# master.net
KiCad netlist of a schematic drawn in Altium Designer
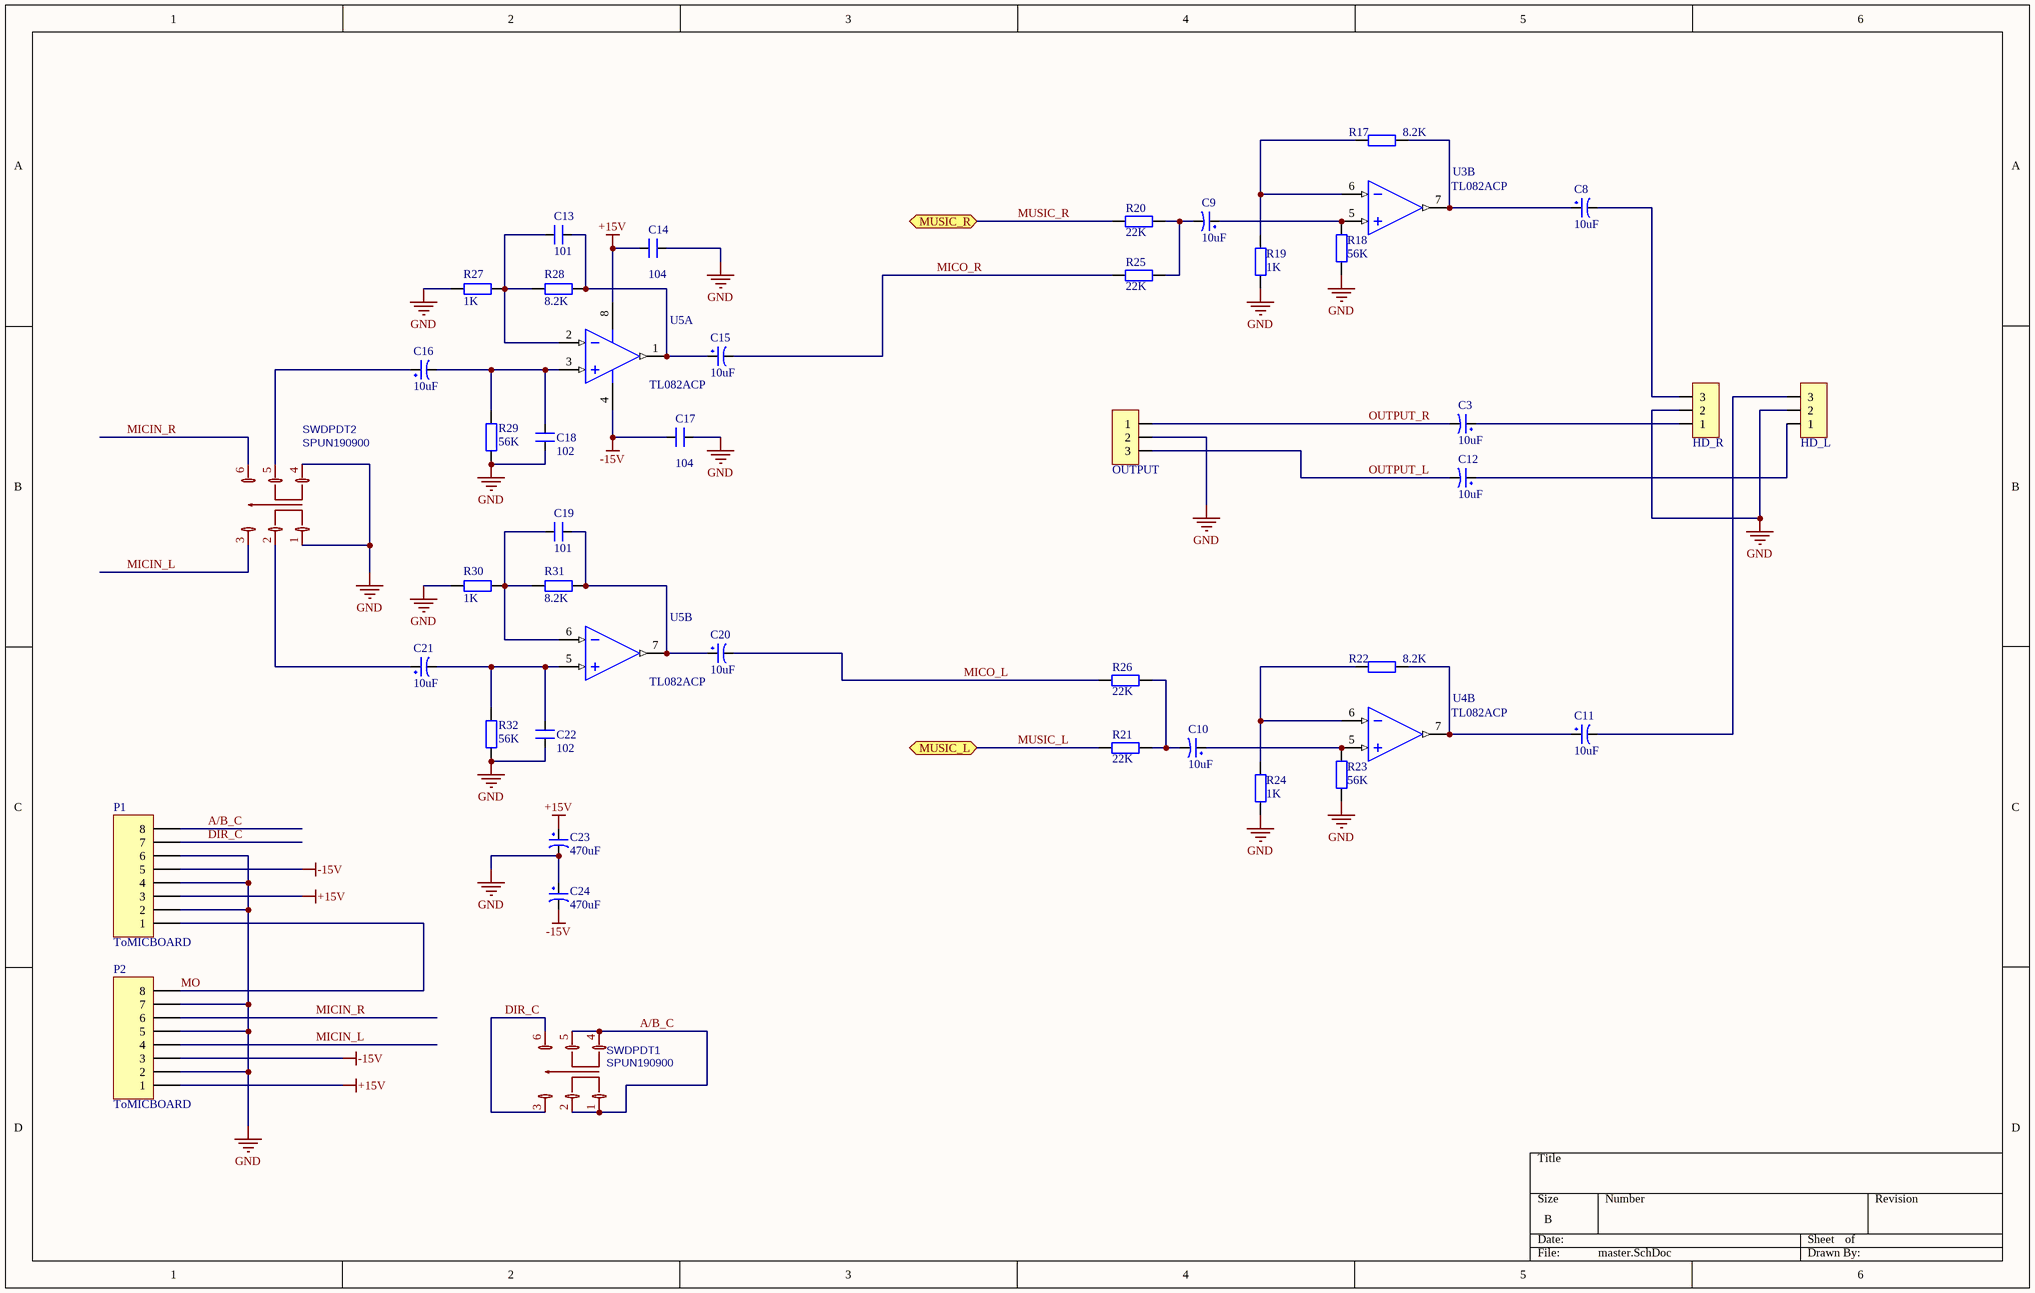
[diagram p0: master.SchDoc]

(export (version "E")
  (design (tool "Eeschema 10.0.6"))
  (components
    (comp (ref "C3")
      (value "10uF")
      (footprint "CAP5x12")
      (description "TU_HOA_4.7uF_100V_MH")
      (libsource (lib "MH_DA_THU_VIEN_16122016") (part "TU_HOA_4.7uF_100V_MH"))
    )
    (comp (ref "C8")
      (value "10uF")
      (footprint "CAP5x12")
      (description "TU_HOA_4.7uF_100V_MH")
      (libsource (lib "MH_DA_THU_VIEN_16122016") (part "TU_HOA_4.7uF_100V_MH"))
    )
    (comp (ref "C9")
      (value "10uF")
      (footprint "CAP5x12")
      (description "TU_HOA_4.7uF_100V_MH")
      (libsource (lib "MH_DA_THU_VIEN_16122016") (part "TU_HOA_4.7uF_100V_MH"))
    )
    (comp (ref "C10")
      (value "10uF")
      (footprint "CAP5x12")
      (description "TU_HOA_4.7uF_100V_MH")
      (libsource (lib "MH_DA_THU_VIEN_16122016") (part "TU_HOA_4.7uF_100V_MH"))
    )
    (comp (ref "C11")
      (value "10uF")
      (footprint "CAP5x12")
      (description "TU_HOA_4.7uF_100V_MH")
      (libsource (lib "MH_DA_THU_VIEN_16122016") (part "TU_HOA_4.7uF_100V_MH"))
    )
    (comp (ref "C12")
      (value "10uF")
      (footprint "CAP5x12")
      (description "TU_HOA_4.7uF_100V_MH")
      (libsource (lib "MH_DA_THU_VIEN_16122016") (part "TU_HOA_4.7uF_100V_MH"))
    )
    (comp (ref "C13")
      (value "101")
      (footprint "TU_GOM(104-->105pF)")
      (libsource (lib "MH_DA_THU_VIEN_16122016") (part "TU_GOM(104 ={gt} 105pF)_MH"))
    )
    (comp (ref "C14")
      (value "104")
      (footprint "TU_GOM(104-->105pF)")
      (libsource (lib "MH_DA_THU_VIEN_16122016") (part "TU_MICA_ 104 100V(2A104J)_MH"))
    )
    (comp (ref "C15")
      (value "10uF")
      (footprint "CAP5x12")
      (description "TU_HOA_4.7uF_100V_MH")
      (libsource (lib "MH_DA_THU_VIEN_16122016") (part "TU_HOA_4.7uF_100V_MH"))
    )
    (comp (ref "C16")
      (value "10uF")
      (footprint "CAP5x12")
      (libsource (lib "MH_DA_THU_VIEN_16122016") (part "TU_HOA_10uF_16V_MH"))
    )
    (comp (ref "C17")
      (value "104")
      (footprint "TU_GOM(104-->105pF)")
      (libsource (lib "MH_DA_THU_VIEN_16122016") (part "TU_MICA_ 104 100V(2A104J)_MH"))
    )
    (comp (ref "C18")
      (value "102")
      (footprint "TU_GOM(104-->105pF)")
      (libsource (lib "MH_DA_THU_VIEN_16122016") (part "TU_GOM(104 ={gt} 105pF)_MH"))
    )
    (comp (ref "C19")
      (value "101")
      (footprint "TU_GOM(104-->105pF)")
      (libsource (lib "MH_DA_THU_VIEN_16122016") (part "TU_GOM(104 ={gt} 105pF)_MH"))
    )
    (comp (ref "C20")
      (value "10uF")
      (footprint "CAP5x12")
      (description "TU_HOA_4.7uF_100V_MH")
      (libsource (lib "MH_DA_THU_VIEN_16122016") (part "TU_HOA_4.7uF_100V_MH"))
    )
    (comp (ref "C21")
      (value "10uF")
      (footprint "CAP5x12")
      (libsource (lib "MH_DA_THU_VIEN_16122016") (part "TU_HOA_10uF_16V_MH"))
    )
    (comp (ref "C22")
      (value "102")
      (footprint "TU_GOM(104-->105pF)")
      (libsource (lib "MH_DA_THU_VIEN_16122016") (part "TU_GOM(104 ={gt} 105pF)_MH"))
    )
    (comp (ref "C23")
      (value "470uF")
      (footprint "TU_HOA(100uF/35V - 470uF/16V)")
      (description "10uF")
      (libsource (lib "") (part "TU_HOA_10uF_16V_MH_1"))
    )
    (comp (ref "C24")
      (value "470uF")
      (footprint "TU_HOA(100uF/35V - 470uF/16V)")
      (description "10uF")
      (libsource (lib "") (part "TU_HOA_10uF_16V_MH_1"))
    )
    (comp (ref "HD_L")
      (value "Header 3_MH")
      (footprint "HEADER 3")
      (description "Header 3P XH2.54 thẳng")
      (libsource (lib "MH_DA_THU_VIEN_16122016") (part "Header 3_MH"))
    )
    (comp (ref "HD_R")
      (value "Header 3_MH")
      (footprint "HEADER 3")
      (description "Header 3P XH2.54 thẳng")
      (libsource (lib "MH_DA_THU_VIEN_16122016") (part "Header 3_MH"))
    )
    (comp (ref "OUTPUT")
      (value "Header 3_MH")
      (footprint "HEADER 3")
      (description "Header 3P XH2.54 thẳng")
      (libsource (lib "") (part "Header 3_MH_1"))
    )
    (comp (ref "P1")
      (value "ToMICBOARD")
      (footprint "HEADER2M_8P")
      (description "Header, 8-Pin")
      (fields (field (name "PUBLISHER") "Altium Limited"))
      (libsource (lib "Miscellaneous Connectors") (part "Header 8"))
    )
    (comp (ref "P2")
      (value "ToMICBOARD")
      (footprint "HEADER 8")
      (description "Header, 8-Pin")
      (fields (field (name "PUBLISHER") "Altium Limited"))
      (libsource (lib "Miscellaneous Connectors") (part "Header 8"))
    )
    (comp (ref "R17")
      (value "8.2K")
      (footprint "TRO_VACH_ 1/4W")
      (description "Resistor")
      (fields (field (name "PUBLISHER") "Altium Limited"))
      (libsource (lib "") (part "TRO_VACH_1/2W_MH_2"))
    )
    (comp (ref "R18")
      (value "56K")
      (footprint "TRO_VACH_ 1/4W")
      (description "Resistor")
      (fields (field (name "PUBLISHER") "Altium Limited"))
      (libsource (lib "MH_DA_THU_VIEN_16122016") (part "TRO_VACH_1/2W_MH"))
    )
    (comp (ref "R19")
      (value "1K")
      (footprint "TRO_VACH_ 1/4W")
      (description "Resistor")
      (fields (field (name "PUBLISHER") "Altium Limited"))
      (libsource (lib "MH_DA_THU_VIEN_16122016") (part "TRO_VACH_1/2W_MH"))
    )
    (comp (ref "R20")
      (value "22K")
      (footprint "TRO_VACH_ 1/4W")
      (description "Resistor")
      (fields (field (name "PUBLISHER") "Altium Limited"))
      (libsource (lib "") (part "TRO_VACH_1/2W_MH_1"))
    )
    (comp (ref "R21")
      (value "22K")
      (footprint "TRO_VACH_ 1/4W")
      (description "Resistor")
      (fields (field (name "PUBLISHER") "Altium Limited"))
      (libsource (lib "") (part "TRO_VACH_1/2W_MH_1"))
    )
    (comp (ref "R22")
      (value "8.2K")
      (footprint "TRO_VACH_ 1/4W")
      (description "Resistor")
      (fields (field (name "PUBLISHER") "Altium Limited"))
      (libsource (lib "") (part "TRO_VACH_1/2W_MH_2"))
    )
    (comp (ref "R23")
      (value "56K")
      (footprint "TRO_VACH_ 1/4W")
      (description "Resistor")
      (fields (field (name "PUBLISHER") "Altium Limited"))
      (libsource (lib "MH_DA_THU_VIEN_16122016") (part "TRO_VACH_1/2W_MH"))
    )
    (comp (ref "R24")
      (value "1K")
      (footprint "TRO_VACH_ 1/4W")
      (description "Resistor")
      (fields (field (name "PUBLISHER") "Altium Limited"))
      (libsource (lib "MH_DA_THU_VIEN_16122016") (part "TRO_VACH_1/2W_MH"))
    )
    (comp (ref "R25")
      (value "22K")
      (footprint "TRO_VACH_ 1/4W")
      (description "Resistor")
      (fields (field (name "PUBLISHER") "Altium Limited"))
      (libsource (lib "") (part "TRO_VACH_1/2W_MH_1"))
    )
    (comp (ref "R26")
      (value "22K")
      (footprint "TRO_VACH_ 1/4W")
      (description "Resistor")
      (fields (field (name "PUBLISHER") "Altium Limited"))
      (libsource (lib "") (part "TRO_VACH_1/2W_MH_1"))
    )
    (comp (ref "R27")
      (value "1K")
      (footprint "TRO_VACH_ 1/4W")
      (libsource (lib "MH_DA_THU_VIEN_16122016") (part "TRO_VACH_1/4W_MH"))
    )
    (comp (ref "R28")
      (value "8.2K")
      (footprint "TRO_VACH_ 1/4W")
      (libsource (lib "MH_DA_THU_VIEN_16122016") (part "TRO_VACH_1/4W_MH"))
    )
    (comp (ref "R29")
      (value "56K")
      (footprint "TRO_VACH_ 1/4W")
      (libsource (lib "MH_DA_THU_VIEN_16122016") (part "TRO_VACH_1/4W_MH"))
    )
    (comp (ref "R30")
      (value "1K")
      (footprint "TRO_VACH_ 1/4W")
      (libsource (lib "MH_DA_THU_VIEN_16122016") (part "TRO_VACH_1/4W_MH"))
    )
    (comp (ref "R31")
      (value "8.2K")
      (footprint "TRO_VACH_ 1/4W")
      (libsource (lib "MH_DA_THU_VIEN_16122016") (part "TRO_VACH_1/4W_MH"))
    )
    (comp (ref "R32")
      (value "56K")
      (footprint "TRO_VACH_ 1/4W")
      (libsource (lib "MH_DA_THU_VIEN_16122016") (part "TRO_VACH_1/4W_MH"))
    )
    (comp (ref "SWDPDT1")
      (value "SPUN190900")
      (footprint "SW-DIP-P42X10")
      (fields (field (name "BOM_SUPPLIER PART") "C278339") (field (name "CONTRIBUTOR") "LCSC"))
      (libsource (lib "Schlib1") (part "SPUN190900"))
    )
    (comp (ref "SWDPDT2")
      (value "SPUN190900")
      (footprint "SW-DIP-P42X10")
      (fields (field (name "BOM_SUPPLIER PART") "C278339") (field (name "CONTRIBUTOR") "LCSC"))
      (libsource (lib "Schlib1") (part "SPUN190900"))
    )
    (comp (ref "U3")
      (value "TL082ACP")
      (footprint "DIP8")
      (description "JFET-Input Operational Amplifier")
      (fields (field (name "PUBLISHER") "Altium Limited"))
      (libsource (lib "Schlib1") (part "TL082ACP"))
    )
    (comp (ref "U4")
      (value "TL082ACP")
      (footprint "DIP8")
      (description "JFET-Input Operational Amplifier")
      (fields (field (name "PUBLISHER") "Altium Limited"))
      (libsource (lib "Schlib1") (part "TL082ACP"))
    )
    (comp (ref "U5")
      (value "TL082ACP")
      (footprint "DIP8")
      (description "JFET-Input Operational Amplifier")
      (fields (field (name "PUBLISHER") "Altium Limited"))
      (libsource (lib "Schlib1") (part "TL082ACP"))
    )
  )
  (nets
    (net (code "1") (name "+15V") (class "Default")
      (node (ref "C14") (pin "1") (pinfunction "1_1") (pintype "passive"))
      (node (ref "C23") (pin "1") (pinfunction "1_1") (pintype "passive"))
      (node (ref "P1") (pin "3") (pinfunction "3_3") (pintype "passive"))
      (node (ref "P2") (pin "1") (pinfunction "1_1") (pintype "passive"))
      (node (ref "U5") (pin "8") (pinfunction "V+_8") (pintype "power_in"))
    )
    (net (code "2") (name "-15V") (class "Default")
      (node (ref "C17") (pin "1") (pinfunction "1_1") (pintype "passive"))
      (node (ref "C24") (pin "2") (pinfunction "2_2") (pintype "passive"))
      (node (ref "P1") (pin "5") (pinfunction "5_5") (pintype "passive"))
      (node (ref "P2") (pin "3") (pinfunction "3_3") (pintype "passive"))
      (node (ref "U5") (pin "4") (pinfunction "V-_4") (pintype "power_in"))
    )
    (net (code "3") (name "/A{slash}B_C") (class "Default")
      (node (ref "P1") (pin "8") (pinfunction "8_8") (pintype "passive"))
      (node (ref "SWDPDT1") (pin "1") (pinfunction "1_1") (pintype "passive"))
      (node (ref "SWDPDT1") (pin "2") (pinfunction "2_2") (pintype "passive"))
      (node (ref "SWDPDT1") (pin "4") (pinfunction "4_4") (pintype "passive"))
      (node (ref "SWDPDT1") (pin "5") (pinfunction "5_5") (pintype "passive"))
    )
    (net (code "4") (name "/DIR_C") (class "Default")
      (node (ref "P1") (pin "7") (pinfunction "7_7") (pintype "passive"))
      (node (ref "SWDPDT1") (pin "3") (pinfunction "3_3") (pintype "passive"))
      (node (ref "SWDPDT1") (pin "6") (pinfunction "6_6") (pintype "passive"))
    )
    (net (code "5") (name "/MICIN_L") (class "Default")
      (node (ref "P2") (pin "4") (pinfunction "4_4") (pintype "passive"))
      (node (ref "SWDPDT2") (pin "3") (pinfunction "3_3") (pintype "passive"))
    )
    (net (code "6") (name "/MICIN_R") (class "Default")
      (node (ref "P2") (pin "6") (pinfunction "6_6") (pintype "passive"))
      (node (ref "SWDPDT2") (pin "6") (pinfunction "6_6") (pintype "passive"))
    )
    (net (code "7") (name "/MICO_L") (class "Default")
      (node (ref "C20") (pin "2") (pinfunction "2_2") (pintype "passive"))
      (node (ref "R26") (pin "1") (pinfunction "1_1") (pintype "passive"))
    )
    (net (code "8") (name "/MICO_R") (class "Default")
      (node (ref "C15") (pin "2") (pinfunction "2_2") (pintype "passive"))
      (node (ref "R25") (pin "1") (pinfunction "1_1") (pintype "passive"))
    )
    (net (code "9") (name "/MO") (class "Default")
      (node (ref "P1") (pin "1") (pinfunction "1_1") (pintype "passive"))
      (node (ref "P2") (pin "8") (pinfunction "8_8") (pintype "passive"))
    )
    (net (code "10") (name "/MUSIC_L") (class "Default")
      (node (ref "R21") (pin "1") (pinfunction "1_1") (pintype "passive"))
    )
    (net (code "11") (name "/MUSIC_R") (class "Default")
      (node (ref "R20") (pin "1") (pinfunction "1_1") (pintype "passive"))
    )
    (net (code "12") (name "/OUTPUT_L") (class "Default")
      (node (ref "C12") (pin "2") (pinfunction "2_2") (pintype "passive"))
      (node (ref "OUTPUT") (pin "3") (pinfunction "3_3") (pintype "passive"))
    )
    (net (code "13") (name "/OUTPUT_R") (class "Default")
      (node (ref "C3") (pin "2") (pinfunction "2_2") (pintype "passive"))
      (node (ref "OUTPUT") (pin "1") (pinfunction "1_1") (pintype "passive"))
    )
    (net (code "14") (name "GND") (class "Default")
      (node (ref "C14") (pin "2") (pinfunction "2_2") (pintype "passive"))
      (node (ref "C17") (pin "2") (pinfunction "2_2") (pintype "passive"))
      (node (ref "C18") (pin "1") (pinfunction "1_1") (pintype "passive"))
      (node (ref "C22") (pin "1") (pinfunction "1_1") (pintype "passive"))
      (node (ref "C23") (pin "2") (pinfunction "2_2") (pintype "passive"))
      (node (ref "C24") (pin "1") (pinfunction "1_1") (pintype "passive"))
      (node (ref "HD_L") (pin "2") (pinfunction "2_2") (pintype "passive"))
      (node (ref "HD_R") (pin "2") (pinfunction "2_2") (pintype "passive"))
      (node (ref "OUTPUT") (pin "2") (pinfunction "2_2") (pintype "passive"))
      (node (ref "P1") (pin "2") (pinfunction "2_2") (pintype "passive"))
      (node (ref "P1") (pin "4") (pinfunction "4_4") (pintype "passive"))
      (node (ref "P1") (pin "6") (pinfunction "6_6") (pintype "passive"))
      (node (ref "P2") (pin "2") (pinfunction "2_2") (pintype "passive"))
      (node (ref "P2") (pin "5") (pinfunction "5_5") (pintype "passive"))
      (node (ref "P2") (pin "7") (pinfunction "7_7") (pintype "passive"))
      (node (ref "R18") (pin "2") (pinfunction "2_2") (pintype "passive"))
      (node (ref "R19") (pin "2") (pinfunction "2_2") (pintype "passive"))
      (node (ref "R23") (pin "2") (pinfunction "2_2") (pintype "passive"))
      (node (ref "R24") (pin "2") (pinfunction "2_2") (pintype "passive"))
      (node (ref "R27") (pin "1") (pinfunction "1_1") (pintype "passive"))
      (node (ref "R29") (pin "1") (pinfunction "1_1") (pintype "passive"))
      (node (ref "R30") (pin "1") (pinfunction "1_1") (pintype "passive"))
      (node (ref "R32") (pin "1") (pinfunction "1_1") (pintype "passive"))
      (node (ref "SWDPDT2") (pin "1") (pinfunction "1_1") (pintype "passive"))
      (node (ref "SWDPDT2") (pin "4") (pinfunction "4_4") (pintype "passive"))
    )
    (net (code "15") (name "Net-(C3-Pad1)") (class "Default")
      (node (ref "C3") (pin "1") (pinfunction "1_1") (pintype "passive"))
      (node (ref "HD_R") (pin "1") (pinfunction "1_1") (pintype "passive"))
    )
    (net (code "16") (name "Net-(C8-Pad2)") (class "Default")
      (node (ref "C8") (pin "2") (pinfunction "2_2") (pintype "passive"))
      (node (ref "HD_R") (pin "3") (pinfunction "3_3") (pintype "passive"))
    )
    (net (code "17") (name "Net-(C9-Pad2)") (class "Default")
      (node (ref "C9") (pin "2") (pinfunction "2_2") (pintype "passive"))
      (node (ref "R20") (pin "2") (pinfunction "2_2") (pintype "passive"))
      (node (ref "R25") (pin "2") (pinfunction "2_2") (pintype "passive"))
    )
    (net (code "18") (name "Net-(C10-Pad2)") (class "Default")
      (node (ref "C10") (pin "2") (pinfunction "2_2") (pintype "passive"))
      (node (ref "R21") (pin "2") (pinfunction "2_2") (pintype "passive"))
      (node (ref "R26") (pin "2") (pinfunction "2_2") (pintype "passive"))
    )
    (net (code "19") (name "Net-(C11-Pad2)") (class "Default")
      (node (ref "C11") (pin "2") (pinfunction "2_2") (pintype "passive"))
      (node (ref "HD_L") (pin "3") (pinfunction "3_3") (pintype "passive"))
    )
    (net (code "20") (name "Net-(C12-Pad1)") (class "Default")
      (node (ref "C12") (pin "1") (pinfunction "1_1") (pintype "passive"))
      (node (ref "HD_L") (pin "1") (pinfunction "1_1") (pintype "passive"))
    )
    (net (code "21") (name "Net-(C16-Pad1)") (class "Default")
      (node (ref "C16") (pin "1") (pinfunction "1_1") (pintype "passive"))
      (node (ref "SWDPDT2") (pin "5") (pinfunction "5_5") (pintype "passive"))
    )
    (net (code "22") (name "Net-(C21-Pad1)") (class "Default")
      (node (ref "C21") (pin "1") (pinfunction "1_1") (pintype "passive"))
      (node (ref "SWDPDT2") (pin "2") (pinfunction "2_2") (pintype "passive"))
    )
    (net (code "23") (name "Net-(U3B-IN+)") (class "Default")
      (node (ref "C9") (pin "1") (pinfunction "1_1") (pintype "passive"))
      (node (ref "R18") (pin "1") (pinfunction "1_1") (pintype "passive"))
      (node (ref "U3") (pin "5") (pinfunction "IN+_5") (pintype "input"))
    )
    (net (code "24") (name "Net-(U3B-IN-)") (class "Default")
      (node (ref "R17") (pin "2") (pinfunction "2_2") (pintype "passive"))
      (node (ref "R19") (pin "1") (pinfunction "1_1") (pintype "passive"))
      (node (ref "U3") (pin "6") (pinfunction "IN-_6") (pintype "input"))
    )
    (net (code "25") (name "Net-(U3B-OUT)") (class "Default")
      (node (ref "C8") (pin "1") (pinfunction "1_1") (pintype "passive"))
      (node (ref "R17") (pin "1") (pinfunction "1_1") (pintype "passive"))
      (node (ref "U3") (pin "7") (pinfunction "OUT_7") (pintype "output"))
    )
    (net (code "26") (name "Net-(U4B-IN+)") (class "Default")
      (node (ref "C10") (pin "1") (pinfunction "1_1") (pintype "passive"))
      (node (ref "R23") (pin "1") (pinfunction "1_1") (pintype "passive"))
      (node (ref "U4") (pin "5") (pinfunction "IN+_5") (pintype "input"))
    )
    (net (code "27") (name "Net-(U4B-IN-)") (class "Default")
      (node (ref "R22") (pin "2") (pinfunction "2_2") (pintype "passive"))
      (node (ref "R24") (pin "1") (pinfunction "1_1") (pintype "passive"))
      (node (ref "U4") (pin "6") (pinfunction "IN-_6") (pintype "input"))
    )
    (net (code "28") (name "Net-(U4B-OUT)") (class "Default")
      (node (ref "C11") (pin "1") (pinfunction "1_1") (pintype "passive"))
      (node (ref "R22") (pin "1") (pinfunction "1_1") (pintype "passive"))
      (node (ref "U4") (pin "7") (pinfunction "OUT_7") (pintype "output"))
    )
    (net (code "29") (name "Net-(U5A-IN+)") (class "Default")
      (node (ref "C16") (pin "2") (pinfunction "2_2") (pintype "passive"))
      (node (ref "C18") (pin "2") (pinfunction "2_2") (pintype "passive"))
      (node (ref "R29") (pin "2") (pinfunction "2_2") (pintype "passive"))
      (node (ref "U5") (pin "3") (pinfunction "IN+_3") (pintype "input"))
    )
    (net (code "30") (name "Net-(U5A-IN-)") (class "Default")
      (node (ref "C13") (pin "2") (pinfunction "2_2") (pintype "passive"))
      (node (ref "R27") (pin "2") (pinfunction "2_2") (pintype "passive"))
      (node (ref "R28") (pin "2") (pinfunction "2_2") (pintype "passive"))
      (node (ref "U5") (pin "2") (pinfunction "IN-_2") (pintype "input"))
    )
    (net (code "31") (name "Net-(U5A-OUT)") (class "Default")
      (node (ref "C13") (pin "1") (pinfunction "1_1") (pintype "passive"))
      (node (ref "C15") (pin "1") (pinfunction "1_1") (pintype "passive"))
      (node (ref "R28") (pin "1") (pinfunction "1_1") (pintype "passive"))
      (node (ref "U5") (pin "1") (pinfunction "OUT_1") (pintype "output"))
    )
    (net (code "32") (name "Net-(U5B-IN+)") (class "Default")
      (node (ref "C21") (pin "2") (pinfunction "2_2") (pintype "passive"))
      (node (ref "C22") (pin "2") (pinfunction "2_2") (pintype "passive"))
      (node (ref "R32") (pin "2") (pinfunction "2_2") (pintype "passive"))
      (node (ref "U5") (pin "5") (pinfunction "IN+_5") (pintype "input"))
    )
    (net (code "33") (name "Net-(U5B-IN-)") (class "Default")
      (node (ref "C19") (pin "2") (pinfunction "2_2") (pintype "passive"))
      (node (ref "R30") (pin "2") (pinfunction "2_2") (pintype "passive"))
      (node (ref "R31") (pin "2") (pinfunction "2_2") (pintype "passive"))
      (node (ref "U5") (pin "6") (pinfunction "IN-_6") (pintype "input"))
    )
    (net (code "34") (name "Net-(U5B-OUT)") (class "Default")
      (node (ref "C19") (pin "1") (pinfunction "1_1") (pintype "passive"))
      (node (ref "C20") (pin "1") (pinfunction "1_1") (pintype "passive"))
      (node (ref "R31") (pin "1") (pinfunction "1_1") (pintype "passive"))
      (node (ref "U5") (pin "7") (pinfunction "OUT_7") (pintype "output"))
    )
  )
)
